# Pulchra_03.net
KiCad netlist of a schematic drawn in EAGLE
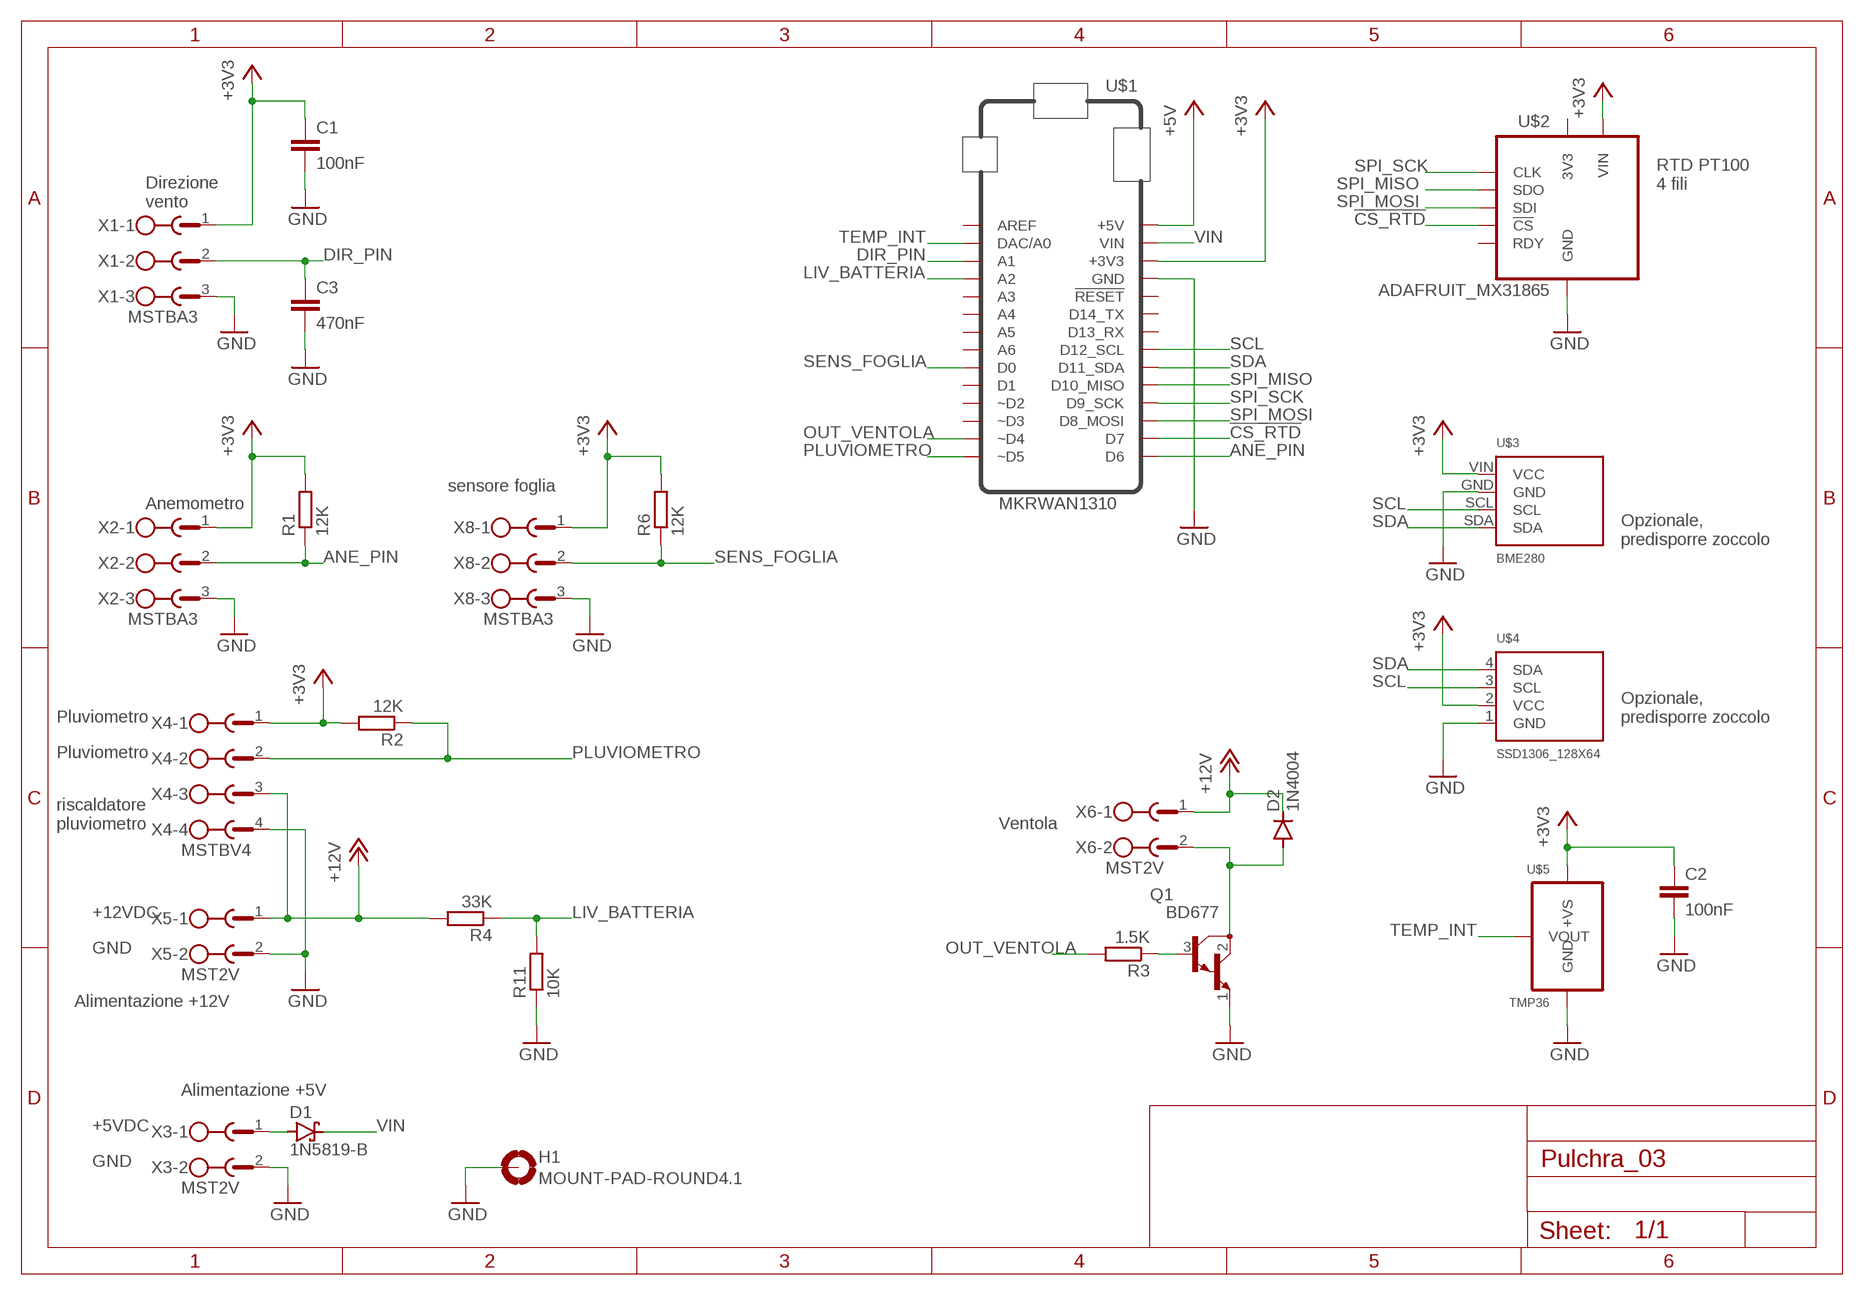
[diagram p0: schematic, sheet 1]

(export (version "E")
  (design (tool "Eeschema 10.0.6"))
  (components
    (comp (ref "C1")
      (value "100nF")
      (footprint "eagle-import:C050-025X075")
      (libsource (lib "eagle-import") (part "C-EU050-025X075"))
    )
    (comp (ref "C2")
      (value "100nF")
      (footprint "eagle-import:C050-025X075")
      (libsource (lib "eagle-import") (part "C-EU050-025X075"))
    )
    (comp (ref "C3")
      (value "470nF")
      (footprint "eagle-import:C050-025X075")
      (libsource (lib "eagle-import") (part "C-EU050-025X075"))
    )
    (comp (ref "D1")
      (value "1N5819-B")
      (footprint "eagle-import:DO41-7.6")
      (libsource (lib "eagle-import") (part "1N5819-B"))
    )
    (comp (ref "D2")
      (value "1N4004")
      (footprint "eagle-import:DO41-10")
      (libsource (lib "eagle-import") (part "1N4004"))
    )
    (comp (ref "H1")
      (value "MOUNT-PAD-ROUND4.1")
      (footprint "eagle-import:4,1-PAD")
      (libsource (lib "eagle-import") (part "MOUNT-PAD-ROUND4.1"))
    )
    (comp (ref "Q1")
      (value "BD677")
      (footprint "eagle-import:TO126")
      (libsource (lib "eagle-import") (part "BD677"))
    )
    (comp (ref "R1")
      (value "12K")
      (footprint "eagle-import:0207_10")
      (libsource (lib "eagle-import") (part "R-EU_0207/10"))
    )
    (comp (ref "R2")
      (value "12K")
      (footprint "eagle-import:0207_10")
      (libsource (lib "eagle-import") (part "R-EU_0207/10"))
    )
    (comp (ref "R3")
      (value "1.5K")
      (footprint "eagle-import:0207_10")
      (libsource (lib "eagle-import") (part "R-EU_0207/10"))
    )
    (comp (ref "R4")
      (value "33K")
      (footprint "eagle-import:0207_10")
      (libsource (lib "eagle-import") (part "R-EU_0207/10"))
    )
    (comp (ref "R6")
      (value "12K")
      (footprint "eagle-import:0207_10")
      (libsource (lib "eagle-import") (part "R-EU_0207/10"))
    )
    (comp (ref "R11")
      (value "10K")
      (footprint "eagle-import:0207_10")
      (libsource (lib "eagle-import") (part "R-EU_0207/10"))
    )
    (comp (ref "U$1")
      (value "MKRWAN1310")
      (footprint "eagle-import:MKRWAN1310")
      (libsource (lib "eagle-import") (part "MKRWAN1310"))
    )
    (comp (ref "U$2")
      (value "ADAFRUIT_MX31865")
      (footprint "eagle-import:ADAFRUIT_MAX31865")
      (libsource (lib "eagle-import") (part "ADAFRUIT_MX31865"))
    )
    (comp (ref "U$3")
      (value "BME280")
      (footprint "eagle-import:BME280_GYBMEP")
      (libsource (lib "eagle-import") (part "BME280"))
    )
    (comp (ref "U$4")
      (value "SSD1306_128X64")
      (footprint "eagle-import:128X64")
      (libsource (lib "eagle-import") (part "SSD1306_128X64"))
    )
    (comp (ref "U$5")
      (value "TMP36")
      (footprint "eagle-import:TO92")
      (libsource (lib "eagle-import") (part "TMP36"))
    )
    (comp (ref "X1")
      (value "MSTBA3")
      (footprint "eagle-import:MSTBA3")
      (fields (field (name "MF") "FARNELL") (field (name "MPN") "1757255"))
      (libsource (lib "eagle-import") (part "MSTBA3"))
    )
    (comp (ref "X2")
      (value "MSTBA3")
      (footprint "eagle-import:MSTBA3")
      (fields (field (name "MF") "FARNELL") (field (name "MPN") "1757255"))
      (libsource (lib "eagle-import") (part "MSTBA3"))
    )
    (comp (ref "X3")
      (value "MST2V")
      (footprint "eagle-import:MSTBV2")
      (libsource (lib "eagle-import") (part "MST2V"))
    )
    (comp (ref "X4")
      (value "MSTBV4")
      (footprint "eagle-import:MSTBV4")
      (fields (field (name "MPN") "MSTBV 2,5/4-GF-5.08"))
      (libsource (lib "eagle-import") (part "MSTBV4"))
    )
    (comp (ref "X5")
      (value "MST2V")
      (footprint "eagle-import:MSTBV2")
      (libsource (lib "eagle-import") (part "MST2V"))
    )
    (comp (ref "X6")
      (value "MST2V")
      (footprint "eagle-import:MSTBV2")
      (libsource (lib "eagle-import") (part "MST2V"))
    )
    (comp (ref "X8")
      (value "MSTBA3")
      (footprint "eagle-import:MSTBA3")
      (fields (field (name "MF") "FARNELL") (field (name "MPN") "1757255"))
      (libsource (lib "eagle-import") (part "MSTBA3"))
    )
  )
  (nets
    (net (code "1") (name "+3V3") (class "Default")
      (node (ref "C1") (pin "1") (pinfunction "1_1") (pintype "passive"))
      (node (ref "C2") (pin "1") (pinfunction "1_1") (pintype "passive"))
      (node (ref "R1") (pin "2") (pinfunction "2_2") (pintype "passive"))
      (node (ref "R2") (pin "2") (pinfunction "2_2") (pintype "passive"))
      (node (ref "R6") (pin "2") (pinfunction "2_2") (pintype "passive"))
      (node (ref "U$1") (pin "+3V3") (pinfunction "+3V3_+3V3") (pintype "power_in"))
      (node (ref "U$2") (pin "P1") (pinfunction "VIN_P1") (pintype "power_in"))
      (node (ref "U$3") (pin "VIN") (pinfunction "VCC_VIN") (pintype "power_in"))
      (node (ref "U$4") (pin "2") (pinfunction "VCC_2") (pintype "power_in"))
      (node (ref "U$5") (pin "1") (pinfunction "+VS_1") (pintype "power_in"))
      (node (ref "X1") (pin "1") (pinfunction "1_1") (pintype "passive"))
      (node (ref "X2") (pin "1") (pinfunction "1_1") (pintype "passive"))
      (node (ref "X4") (pin "1") (pinfunction "1_1") (pintype "passive"))
      (node (ref "X8") (pin "1") (pinfunction "1_1") (pintype "passive"))
    )
    (net (code "2") (name "+5V") (class "Default")
      (node (ref "U$1") (pin "+5V") (pinfunction "+5V_+5V") (pintype "power_in"))
    )
    (net (code "3") (name "+12V") (class "Default")
      (node (ref "D2") (pin "C") (pinfunction "C_C") (pintype "passive"))
      (node (ref "R4") (pin "2") (pinfunction "2_2") (pintype "passive"))
      (node (ref "X4") (pin "3") (pinfunction "1_3") (pintype "passive"))
      (node (ref "X5") (pin "1") (pinfunction "1_1") (pintype "passive"))
      (node (ref "X6") (pin "1") (pinfunction "1_1") (pintype "passive"))
    )
    (net (code "4") (name "/ANE_PIN") (class "Default")
      (node (ref "R1") (pin "1") (pinfunction "1_1") (pintype "passive"))
      (node (ref "U$1") (pin "D6") (pinfunction "D6_D6") (pintype "bidirectional"))
      (node (ref "X2") (pin "2") (pinfunction "1_2") (pintype "passive"))
    )
    (net (code "5") (name "/DIR_PIN") (class "Default")
      (node (ref "C3") (pin "1") (pinfunction "1_1") (pintype "passive"))
      (node (ref "U$1") (pin "A1") (pinfunction "A1_A1") (pintype "input"))
      (node (ref "X1") (pin "2") (pinfunction "1_2") (pintype "passive"))
    )
    (net (code "6") (name "/LIV_BATTERIA") (class "Default")
      (node (ref "R11") (pin "2") (pinfunction "2_2") (pintype "passive"))
      (node (ref "R4") (pin "1") (pinfunction "1_1") (pintype "passive"))
      (node (ref "U$1") (pin "A2") (pinfunction "A2_A2") (pintype "input"))
    )
    (net (code "7") (name "/OUT_VENTOLA") (class "Default")
      (node (ref "R3") (pin "2") (pinfunction "2_2") (pintype "passive"))
      (node (ref "U$1") (pin "~D4") (pinfunction "~{D4}_~D4") (pintype "bidirectional"))
    )
    (net (code "8") (name "/PLUVIOMETRO") (class "Default")
      (node (ref "R2") (pin "1") (pinfunction "1_1") (pintype "passive"))
      (node (ref "U$1") (pin "~D5") (pinfunction "~{D5}_~D5") (pintype "bidirectional"))
      (node (ref "X4") (pin "2") (pinfunction "1_2") (pintype "passive"))
    )
    (net (code "9") (name "/SCL") (class "Default")
      (node (ref "U$1") (pin "D12_SCL") (pinfunction "D12_SCL_D12_SCL") (pintype "bidirectional"))
      (node (ref "U$3") (pin "SCL") (pinfunction "SCL_SCL") (pintype "bidirectional"))
      (node (ref "U$4") (pin "3") (pinfunction "SCL_3") (pintype "bidirectional"))
    )
    (net (code "10") (name "/SDA") (class "Default")
      (node (ref "U$1") (pin "D11_SDA") (pinfunction "D11_SDA_D11_SDA") (pintype "bidirectional"))
      (node (ref "U$3") (pin "SDA") (pinfunction "SDA_SDA") (pintype "bidirectional"))
      (node (ref "U$4") (pin "4") (pinfunction "SDA_4") (pintype "bidirectional"))
    )
    (net (code "11") (name "/SENS_FOGLIA") (class "Default")
      (node (ref "R6") (pin "1") (pinfunction "1_1") (pintype "passive"))
      (node (ref "U$1") (pin "D0") (pinfunction "D0_D0") (pintype "bidirectional"))
      (node (ref "X8") (pin "2") (pinfunction "1_2") (pintype "passive"))
    )
    (net (code "12") (name "/SPI_MISO") (class "Default")
      (node (ref "U$1") (pin "D10_MISO") (pinfunction "D10_MISO_D10_MISO") (pintype "bidirectional"))
      (node (ref "U$2") (pin "P5") (pinfunction "SDO_P5") (pintype "output"))
    )
    (net (code "13") (name "/SPI_MOSI") (class "Default")
      (node (ref "U$1") (pin "D8_MOSI") (pinfunction "D8_MOSI_D8_MOSI") (pintype "bidirectional"))
      (node (ref "U$2") (pin "P6") (pinfunction "SDI_P6") (pintype "input"))
    )
    (net (code "14") (name "/SPI_SCK") (class "Default")
      (node (ref "U$1") (pin "D9_SCK") (pinfunction "D9_SCK_D9_SCK") (pintype "bidirectional"))
      (node (ref "U$2") (pin "P4") (pinfunction "CLK_P4") (pintype "input"))
    )
    (net (code "15") (name "/TEMP_INT") (class "Default")
      (node (ref "U$1") (pin "DAC0/A0") (pinfunction "DAC/A0_DAC0/A0") (pintype "input"))
      (node (ref "U$5") (pin "2") (pinfunction "VOUT_2") (pintype "output"))
    )
    (net (code "16") (name "/VIN") (class "Default")
      (node (ref "D1") (pin "C") (pinfunction "C_C") (pintype "passive"))
      (node (ref "U$1") (pin "VIN") (pinfunction "VIN_VIN") (pintype "power_in"))
    )
    (net (code "17") (name "/~{CS_RTD}") (class "Default")
      (node (ref "U$1") (pin "D7") (pinfunction "D7_D7") (pintype "bidirectional"))
      (node (ref "U$2") (pin "P7") (pinfunction "~{CS}_P7") (pintype "input"))
    )
    (net (code "18") (name "GND") (class "Default")
      (node (ref "C1") (pin "2") (pinfunction "2_2") (pintype "passive"))
      (node (ref "C2") (pin "2") (pinfunction "2_2") (pintype "passive"))
      (node (ref "C3") (pin "2") (pinfunction "2_2") (pintype "passive"))
      (node (ref "H1") (pin "B4,1") (pinfunction "MOUNT_B4,1") (pintype "passive"))
      (node (ref "Q1") (pin "1") (pinfunction "E_1") (pintype "passive"))
      (node (ref "R11") (pin "1") (pinfunction "1_1") (pintype "passive"))
      (node (ref "U$1") (pin "GND") (pinfunction "GND_GND") (pintype "power_in"))
      (node (ref "U$2") (pin "P2") (pinfunction "GND_P2") (pintype "power_in"))
      (node (ref "U$3") (pin "GND") (pinfunction "GND_GND") (pintype "power_in"))
      (node (ref "U$4") (pin "1") (pinfunction "GND_1") (pintype "power_in"))
      (node (ref "U$5") (pin "3") (pinfunction "GND_3") (pintype "power_in"))
      (node (ref "X1") (pin "3") (pinfunction "1_3") (pintype "passive"))
      (node (ref "X2") (pin "3") (pinfunction "1_3") (pintype "passive"))
      (node (ref "X3") (pin "2") (pinfunction "1_2") (pintype "passive"))
      (node (ref "X4") (pin "4") (pinfunction "1_4") (pintype "passive"))
      (node (ref "X5") (pin "2") (pinfunction "1_2") (pintype "passive"))
      (node (ref "X8") (pin "3") (pinfunction "1_3") (pintype "passive"))
    )
    (net (code "19") (name "Net-(D1-PadA)") (class "Default")
      (node (ref "D1") (pin "A") (pinfunction "A_A") (pintype "passive"))
      (node (ref "X3") (pin "1") (pinfunction "1_1") (pintype "passive"))
    )
    (net (code "20") (name "Net-(Q1-B)") (class "Default")
      (node (ref "Q1") (pin "3") (pinfunction "B_3") (pintype "passive"))
      (node (ref "R3") (pin "1") (pinfunction "1_1") (pintype "passive"))
    )
    (net (code "21") (name "Net-(Q1-C)") (class "Default")
      (node (ref "D2") (pin "A") (pinfunction "A_A") (pintype "passive"))
      (node (ref "Q1") (pin "2") (pinfunction "C_2") (pintype "passive"))
      (node (ref "X6") (pin "2") (pinfunction "1_2") (pintype "passive"))
    )
    (net (code "22") (name "unconnected-(U$1-PadA3)") (class "Default")
      (node (ref "U$1") (pin "A3") (pinfunction "A3_A3") (pintype "input"))
    )
    (net (code "23") (name "unconnected-(U$1-PadA4)") (class "Default")
      (node (ref "U$1") (pin "A4") (pinfunction "A4_A4") (pintype "input"))
    )
    (net (code "24") (name "unconnected-(U$1-PadA5)") (class "Default")
      (node (ref "U$1") (pin "A5") (pinfunction "A5_A5") (pintype "input"))
    )
    (net (code "25") (name "unconnected-(U$1-PadA6)") (class "Default")
      (node (ref "U$1") (pin "A6") (pinfunction "A6_A6") (pintype "input"))
    )
    (net (code "26") (name "unconnected-(U$1-PadAREF)") (class "Default")
      (node (ref "U$1") (pin "AREF") (pinfunction "AREF_AREF") (pintype "passive"))
    )
    (net (code "27") (name "unconnected-(U$1-PadD1)") (class "Default")
      (node (ref "U$1") (pin "D1") (pinfunction "D1_D1") (pintype "bidirectional"))
    )
    (net (code "28") (name "unconnected-(U$1-PadD13_RX)") (class "Default")
      (node (ref "U$1") (pin "D13_RX") (pinfunction "D13_RX_D13_RX") (pintype "bidirectional"))
    )
    (net (code "29") (name "unconnected-(U$1-PadD14_TX)") (class "Default")
      (node (ref "U$1") (pin "D14_TX") (pinfunction "D14_TX_D14_TX") (pintype "bidirectional"))
    )
    (net (code "30") (name "unconnected-(U$1-~{D2}-Pad~D2)") (class "Default")
      (node (ref "U$1") (pin "~D2") (pinfunction "~{D2}_~D2") (pintype "bidirectional"))
    )
    (net (code "31") (name "unconnected-(U$1-~{D3}-Pad~D3)") (class "Default")
      (node (ref "U$1") (pin "~D3") (pinfunction "~{D3}_~D3") (pintype "bidirectional"))
    )
    (net (code "32") (name "unconnected-(U$1-~{RESET}-Pad!RESET!)") (class "Default")
      (node (ref "U$1") (pin "!RESET!") (pinfunction "~{RESET}_!RESET!") (pintype "input"))
    )
    (net (code "33") (name "unconnected-(U$2-3V3-PadP3)") (class "Default")
      (node (ref "U$2") (pin "P3") (pinfunction "3V3_P3") (pintype "output"))
    )
    (net (code "34") (name "unconnected-(U$2-RDY-PadP8)") (class "Default")
      (node (ref "U$2") (pin "P8") (pinfunction "RDY_P8") (pintype "output"))
    )
  )
)
